# temp_sub_module.net
KiCad netlist of a schematic drawn in EAGLE
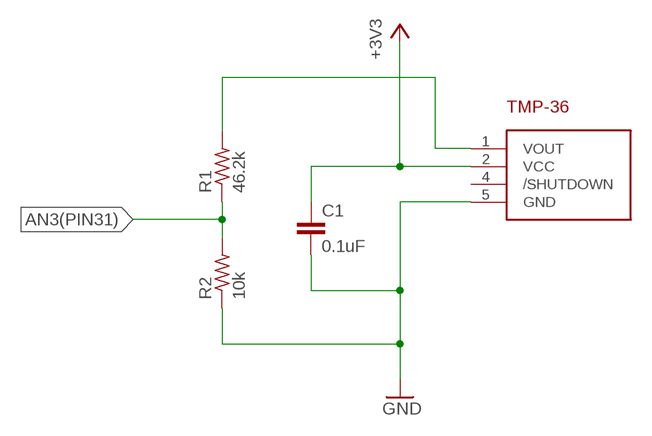
[diagram p0: schematic, sheet 1]

(export (version "E")
  (design (tool "Eeschema 10.0.6"))
  (components
    (comp (ref "C1")
      (value "0.1uF")
      (footprint "eagle-import:C025-024X044")
      (libsource (lib "eagle-import") (part "C-EU025-024X044"))
    )
    (comp (ref "R1")
      (value "46.2k")
      (footprint "eagle-import:0204V")
      (libsource (lib "eagle-import") (part "R-US_0204/2V"))
    )
    (comp (ref "R2")
      (value "10k")
      (footprint "eagle-import:0204V")
      (libsource (lib "eagle-import") (part "R-US_0204/2V"))
    )
    (comp (ref "U$1")
      (value "TMP36")
      (footprint "eagle-import:SOT-23")
      (libsource (lib "eagle-import") (part "TMP36"))
    )
  )
  (nets
    (net (code "1") (name "+3V3") (class "Default")
      (node (ref "C1") (pin "1") (pinfunction "1_1") (pintype "passive"))
      (node (ref "U$1") (pin "2") (pinfunction "VCC_2") (pintype "bidirectional"))
    )
    (net (code "2") (name "AN3(PIN31)") (class "Default")
      (node (ref "R1") (pin "1") (pinfunction "1_1") (pintype "passive"))
      (node (ref "R2") (pin "2") (pinfunction "2_2") (pintype "passive"))
    )
    (net (code "3") (name "GND") (class "Default")
      (node (ref "C1") (pin "2") (pinfunction "2_2") (pintype "passive"))
      (node (ref "R2") (pin "1") (pinfunction "1_1") (pintype "passive"))
      (node (ref "U$1") (pin "5") (pinfunction "GND_5") (pintype "bidirectional"))
    )
    (net (code "4") (name "Net-(U$1-VOUT)") (class "Default")
      (node (ref "R1") (pin "2") (pinfunction "2_2") (pintype "passive"))
      (node (ref "U$1") (pin "1") (pinfunction "VOUT_1") (pintype "bidirectional"))
    )
    (net (code "5") (name "unconnected-(U$1-{slash}SHUTDOWN-Pad4)") (class "Default")
      (node (ref "U$1") (pin "4") (pinfunction "/SHUTDOWN_4") (pintype "bidirectional"))
    )
  )
)
